# ARUDUINO128-3.net
KiCad netlist of a schematic drawn in EAGLE
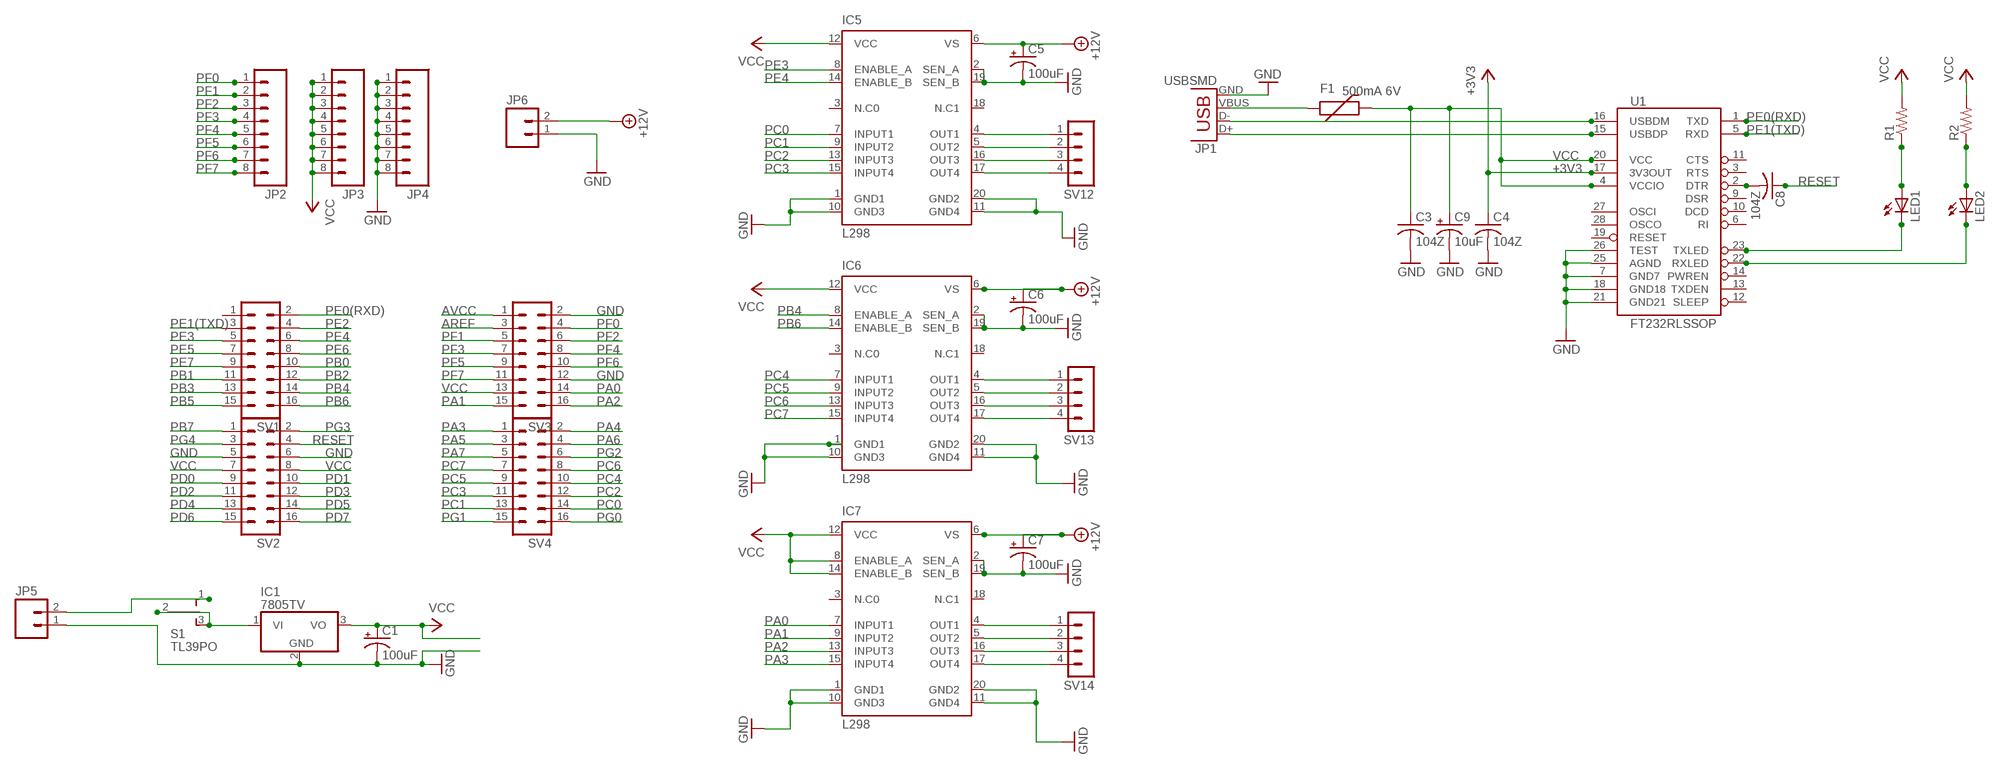
[diagram p0: schematic, sheet 1]

(export (version "E")
  (design (tool "Eeschema 10.0.6"))
  (components
    (comp (ref "C1")
      (value "100uF")
      (footprint "eagle-import:153CLV-0807")
      (libsource (lib "eagle-import") (part "CPOL-US153CLV-0807"))
    )
    (comp (ref "C3")
      (value "104Z")
      (footprint "eagle-import:C0603K")
      (libsource (lib "eagle-import") (part "C-USC0603K"))
    )
    (comp (ref "C4")
      (value "104Z")
      (footprint "eagle-import:C0603K")
      (libsource (lib "eagle-import") (part "C-USC0603K"))
    )
    (comp (ref "C5")
      (value "100uF")
      (footprint "eagle-import:153CLV-0807")
      (libsource (lib "eagle-import") (part "CPOL-US153CLV-0807"))
    )
    (comp (ref "C6")
      (value "100uF")
      (footprint "eagle-import:153CLV-0807")
      (libsource (lib "eagle-import") (part "CPOL-US153CLV-0807"))
    )
    (comp (ref "C7")
      (value "100uF")
      (footprint "eagle-import:153CLV-0807")
      (libsource (lib "eagle-import") (part "CPOL-US153CLV-0807"))
    )
    (comp (ref "C8")
      (value "104Z")
      (footprint "eagle-import:C0603K")
      (libsource (lib "eagle-import") (part "C-USC0603K"))
    )
    (comp (ref "C9")
      (value "10uF")
      (footprint "eagle-import:A_3216-18W")
      (libsource (lib "eagle-import") (part "CPOL-USA/3216-18W"))
    )
    (comp (ref "F1")
      (value "500mA 6V")
      (footprint "eagle-import:PTC-1206")
      (libsource (lib "eagle-import") (part "PTCSMD"))
    )
    (comp (ref "IC1")
      (value "7805TV")
      (footprint "eagle-import:TO220V")
      (libsource (lib "eagle-import") (part "78TV05"))
    )
    (comp (ref "IC5")
      (value "L298")
      (footprint "eagle-import:POWERSO-20")
      (libsource (lib "eagle-import") (part "L298"))
    )
    (comp (ref "IC6")
      (value "L298")
      (footprint "eagle-import:POWERSO-20")
      (libsource (lib "eagle-import") (part "L298"))
    )
    (comp (ref "IC7")
      (value "L298")
      (footprint "eagle-import:POWERSO-20")
      (libsource (lib "eagle-import") (part "L298"))
    )
    (comp (ref "JP1")
      (value "USBSMD")
      (footprint "eagle-import:USB-MINIB")
      (libsource (lib "eagle-import") (part "USBSMD"))
    )
    (comp (ref "JP2")
      (value "M08")
      (footprint "eagle-import:1X08_ROUND")
      (libsource (lib "eagle-import") (part "M08"))
    )
    (comp (ref "JP3")
      (value "M08")
      (footprint "eagle-import:1X08_ROUND")
      (libsource (lib "eagle-import") (part "M08"))
    )
    (comp (ref "JP4")
      (value "M08")
      (footprint "eagle-import:1X08_ROUND")
      (libsource (lib "eagle-import") (part "M08"))
    )
    (comp (ref "JP5")
      (value "M02PTH")
      (footprint "eagle-import:1X02")
      (libsource (lib "eagle-import") (part "M02PTH"))
    )
    (comp (ref "JP6")
      (value "M02PTH")
      (footprint "eagle-import:1X02")
      (libsource (lib "eagle-import") (part "M02PTH"))
    )
    (comp (ref "LED1")
      (value "LEDCHIPLED_0603")
      (footprint "eagle-import:CHIPLED_0603")
      (libsource (lib "eagle-import") (part "LEDCHIPLED_0603"))
    )
    (comp (ref "LED2")
      (value "LEDCHIPLED_0603")
      (footprint "eagle-import:CHIPLED_0603")
      (libsource (lib "eagle-import") (part "LEDCHIPLED_0603"))
    )
    (comp (ref "R1")
      (value "R-US_M0805")
      (footprint "eagle-import:M0805")
      (libsource (lib "eagle-import") (part "R-US_M0805"))
    )
    (comp (ref "R2")
      (value "R-US_M0805")
      (footprint "eagle-import:M0805")
      (libsource (lib "eagle-import") (part "R-US_M0805"))
    )
    (comp (ref "S1")
      (value "TL39PO")
      (footprint "eagle-import:TL3XPO")
      (libsource (lib "eagle-import") (part "TL39PO"))
    )
    (comp (ref "SV1")
      (value "MA08-2")
      (footprint "eagle-import:MA08-2")
      (libsource (lib "eagle-import") (part "MA08-2"))
    )
    (comp (ref "SV2")
      (value "MA08-2")
      (footprint "eagle-import:MA08-2")
      (libsource (lib "eagle-import") (part "MA08-2"))
    )
    (comp (ref "SV3")
      (value "MA08-2")
      (footprint "eagle-import:MA08-2")
      (libsource (lib "eagle-import") (part "MA08-2"))
    )
    (comp (ref "SV4")
      (value "MA08-2")
      (footprint "eagle-import:MA08-2")
      (libsource (lib "eagle-import") (part "MA08-2"))
    )
    (comp (ref "SV12")
      (value "MA04-1")
      (footprint "eagle-import:MA04-1")
      (libsource (lib "eagle-import") (part "MA04-1"))
    )
    (comp (ref "SV13")
      (value "MA04-1")
      (footprint "eagle-import:MA04-1")
      (libsource (lib "eagle-import") (part "MA04-1"))
    )
    (comp (ref "SV14")
      (value "MA04-1")
      (footprint "eagle-import:MA04-1")
      (libsource (lib "eagle-import") (part "MA04-1"))
    )
    (comp (ref "U1")
      (value "FT232RLSSOP")
      (footprint "eagle-import:SSOP28DB")
      (libsource (lib "eagle-import") (part "FT232RLSSOP"))
    )
  )
  (nets
    (net (code "1") (name "+3V3") (class "Default")
      (node (ref "C4") (pin "1") (pinfunction "1_1") (pintype "passive"))
      (node (ref "U1") (pin "17") (pinfunction "3V3OUT_17") (pintype "output"))
    )
    (net (code "2") (name "+12V") (class "Default")
      (node (ref "C5") (pin "+") (pinfunction "+_+") (pintype "passive"))
      (node (ref "C6") (pin "+") (pinfunction "+_+") (pintype "passive"))
      (node (ref "C7") (pin "+") (pinfunction "+_+") (pintype "passive"))
      (node (ref "IC5") (pin "6") (pinfunction "VS_6") (pintype "power_in"))
      (node (ref "IC6") (pin "6") (pinfunction "VS_6") (pintype "power_in"))
      (node (ref "IC7") (pin "6") (pinfunction "VS_6") (pintype "power_in"))
      (node (ref "JP6") (pin "2") (pinfunction "2_2") (pintype "passive"))
    )
    (net (code "3") (name "/AREF") (class "Default")
      (node (ref "SV3") (pin "3") (pinfunction "3_3") (pintype "passive"))
    )
    (net (code "4") (name "/AVCC") (class "Default")
      (node (ref "SV3") (pin "1") (pinfunction "1_1") (pintype "passive"))
    )
    (net (code "5") (name "/PA0") (class "Default")
      (node (ref "IC7") (pin "7") (pinfunction "INPUT1_7") (pintype "input"))
      (node (ref "SV3") (pin "14") (pinfunction "14_14") (pintype "passive"))
    )
    (net (code "6") (name "/PA1") (class "Default")
      (node (ref "IC7") (pin "9") (pinfunction "INPUT2_9") (pintype "input"))
      (node (ref "SV3") (pin "15") (pinfunction "15_15") (pintype "passive"))
    )
    (net (code "7") (name "/PA2") (class "Default")
      (node (ref "IC7") (pin "13") (pinfunction "INPUT3_13") (pintype "input"))
      (node (ref "SV3") (pin "16") (pinfunction "16_16") (pintype "passive"))
    )
    (net (code "8") (name "/PA3") (class "Default")
      (node (ref "IC7") (pin "15") (pinfunction "INPUT4_15") (pintype "input"))
      (node (ref "SV4") (pin "1") (pinfunction "1_1") (pintype "passive"))
    )
    (net (code "9") (name "/PA4") (class "Default")
      (node (ref "SV4") (pin "2") (pinfunction "2_2") (pintype "passive"))
    )
    (net (code "10") (name "/PA5") (class "Default")
      (node (ref "SV4") (pin "3") (pinfunction "3_3") (pintype "passive"))
    )
    (net (code "11") (name "/PA6") (class "Default")
      (node (ref "SV4") (pin "4") (pinfunction "4_4") (pintype "passive"))
    )
    (net (code "12") (name "/PA7") (class "Default")
      (node (ref "SV4") (pin "5") (pinfunction "5_5") (pintype "passive"))
    )
    (net (code "13") (name "/PB0") (class "Default")
      (node (ref "SV1") (pin "10") (pinfunction "10_10") (pintype "passive"))
    )
    (net (code "14") (name "/PB1") (class "Default")
      (node (ref "SV1") (pin "11") (pinfunction "11_11") (pintype "passive"))
    )
    (net (code "15") (name "/PB2") (class "Default")
      (node (ref "SV1") (pin "12") (pinfunction "12_12") (pintype "passive"))
    )
    (net (code "16") (name "/PB3") (class "Default")
      (node (ref "SV1") (pin "13") (pinfunction "13_13") (pintype "passive"))
    )
    (net (code "17") (name "/PB4") (class "Default")
      (node (ref "IC6") (pin "8") (pinfunction "ENABLE_A_8") (pintype "input"))
      (node (ref "SV1") (pin "14") (pinfunction "14_14") (pintype "passive"))
    )
    (net (code "18") (name "/PB5") (class "Default")
      (node (ref "SV1") (pin "15") (pinfunction "15_15") (pintype "passive"))
    )
    (net (code "19") (name "/PB6") (class "Default")
      (node (ref "IC6") (pin "14") (pinfunction "ENABLE_B_14") (pintype "input"))
      (node (ref "SV1") (pin "16") (pinfunction "16_16") (pintype "passive"))
    )
    (net (code "20") (name "/PB7") (class "Default")
      (node (ref "SV2") (pin "1") (pinfunction "1_1") (pintype "passive"))
    )
    (net (code "21") (name "/PC0") (class "Default")
      (node (ref "IC5") (pin "7") (pinfunction "INPUT1_7") (pintype "input"))
      (node (ref "SV4") (pin "14") (pinfunction "14_14") (pintype "passive"))
    )
    (net (code "22") (name "/PC1") (class "Default")
      (node (ref "IC5") (pin "9") (pinfunction "INPUT2_9") (pintype "input"))
      (node (ref "SV4") (pin "13") (pinfunction "13_13") (pintype "passive"))
    )
    (net (code "23") (name "/PC2") (class "Default")
      (node (ref "IC5") (pin "13") (pinfunction "INPUT3_13") (pintype "input"))
      (node (ref "SV4") (pin "12") (pinfunction "12_12") (pintype "passive"))
    )
    (net (code "24") (name "/PC3") (class "Default")
      (node (ref "IC5") (pin "15") (pinfunction "INPUT4_15") (pintype "input"))
      (node (ref "SV4") (pin "11") (pinfunction "11_11") (pintype "passive"))
    )
    (net (code "25") (name "/PC4") (class "Default")
      (node (ref "IC6") (pin "7") (pinfunction "INPUT1_7") (pintype "input"))
      (node (ref "SV4") (pin "10") (pinfunction "10_10") (pintype "passive"))
    )
    (net (code "26") (name "/PC5") (class "Default")
      (node (ref "IC6") (pin "9") (pinfunction "INPUT2_9") (pintype "input"))
      (node (ref "SV4") (pin "9") (pinfunction "9_9") (pintype "passive"))
    )
    (net (code "27") (name "/PC6") (class "Default")
      (node (ref "IC6") (pin "13") (pinfunction "INPUT3_13") (pintype "input"))
      (node (ref "SV4") (pin "8") (pinfunction "8_8") (pintype "passive"))
    )
    (net (code "28") (name "/PC7") (class "Default")
      (node (ref "IC6") (pin "15") (pinfunction "INPUT4_15") (pintype "input"))
      (node (ref "SV4") (pin "7") (pinfunction "7_7") (pintype "passive"))
    )
    (net (code "29") (name "/PD0") (class "Default")
      (node (ref "SV2") (pin "9") (pinfunction "9_9") (pintype "passive"))
    )
    (net (code "30") (name "/PD1") (class "Default")
      (node (ref "SV2") (pin "10") (pinfunction "10_10") (pintype "passive"))
    )
    (net (code "31") (name "/PD2") (class "Default")
      (node (ref "SV2") (pin "11") (pinfunction "11_11") (pintype "passive"))
    )
    (net (code "32") (name "/PD3") (class "Default")
      (node (ref "SV2") (pin "12") (pinfunction "12_12") (pintype "passive"))
    )
    (net (code "33") (name "/PD4") (class "Default")
      (node (ref "SV2") (pin "13") (pinfunction "13_13") (pintype "passive"))
    )
    (net (code "34") (name "/PD5") (class "Default")
      (node (ref "SV2") (pin "14") (pinfunction "14_14") (pintype "passive"))
    )
    (net (code "35") (name "/PD6") (class "Default")
      (node (ref "SV2") (pin "15") (pinfunction "15_15") (pintype "passive"))
    )
    (net (code "36") (name "/PD7") (class "Default")
      (node (ref "SV2") (pin "16") (pinfunction "16_16") (pintype "passive"))
    )
    (net (code "37") (name "/PE0(RXD)") (class "Default")
      (node (ref "SV1") (pin "2") (pinfunction "2_2") (pintype "passive"))
      (node (ref "U1") (pin "1") (pinfunction "TXD_1") (pintype "output"))
    )
    (net (code "38") (name "/PE1(TXD)") (class "Default")
      (node (ref "SV1") (pin "3") (pinfunction "3_3") (pintype "passive"))
      (node (ref "U1") (pin "5") (pinfunction "RXD_5") (pintype "input"))
    )
    (net (code "39") (name "/PE2") (class "Default")
      (node (ref "SV1") (pin "4") (pinfunction "4_4") (pintype "passive"))
    )
    (net (code "40") (name "/PE3") (class "Default")
      (node (ref "IC5") (pin "8") (pinfunction "ENABLE_A_8") (pintype "input"))
      (node (ref "SV1") (pin "5") (pinfunction "5_5") (pintype "passive"))
    )
    (net (code "41") (name "/PE4") (class "Default")
      (node (ref "IC5") (pin "14") (pinfunction "ENABLE_B_14") (pintype "input"))
      (node (ref "SV1") (pin "6") (pinfunction "6_6") (pintype "passive"))
    )
    (net (code "42") (name "/PE5") (class "Default")
      (node (ref "SV1") (pin "7") (pinfunction "7_7") (pintype "passive"))
    )
    (net (code "43") (name "/PE6") (class "Default")
      (node (ref "SV1") (pin "8") (pinfunction "8_8") (pintype "passive"))
    )
    (net (code "44") (name "/PE7") (class "Default")
      (node (ref "SV1") (pin "9") (pinfunction "9_9") (pintype "passive"))
    )
    (net (code "45") (name "/PF0") (class "Default")
      (node (ref "JP2") (pin "1") (pinfunction "1_1") (pintype "passive"))
      (node (ref "SV3") (pin "4") (pinfunction "4_4") (pintype "passive"))
    )
    (net (code "46") (name "/PF1") (class "Default")
      (node (ref "JP2") (pin "2") (pinfunction "2_2") (pintype "passive"))
      (node (ref "SV3") (pin "5") (pinfunction "5_5") (pintype "passive"))
    )
    (net (code "47") (name "/PF2") (class "Default")
      (node (ref "JP2") (pin "3") (pinfunction "3_3") (pintype "passive"))
      (node (ref "SV3") (pin "6") (pinfunction "6_6") (pintype "passive"))
    )
    (net (code "48") (name "/PF3") (class "Default")
      (node (ref "JP2") (pin "4") (pinfunction "4_4") (pintype "passive"))
      (node (ref "SV3") (pin "7") (pinfunction "7_7") (pintype "passive"))
    )
    (net (code "49") (name "/PF4") (class "Default")
      (node (ref "JP2") (pin "5") (pinfunction "5_5") (pintype "passive"))
      (node (ref "SV3") (pin "8") (pinfunction "8_8") (pintype "passive"))
    )
    (net (code "50") (name "/PF5") (class "Default")
      (node (ref "JP2") (pin "6") (pinfunction "6_6") (pintype "passive"))
      (node (ref "SV3") (pin "9") (pinfunction "9_9") (pintype "passive"))
    )
    (net (code "51") (name "/PF6") (class "Default")
      (node (ref "JP2") (pin "7") (pinfunction "7_7") (pintype "passive"))
      (node (ref "SV3") (pin "10") (pinfunction "10_10") (pintype "passive"))
    )
    (net (code "52") (name "/PF7") (class "Default")
      (node (ref "JP2") (pin "8") (pinfunction "8_8") (pintype "passive"))
      (node (ref "SV3") (pin "11") (pinfunction "11_11") (pintype "passive"))
    )
    (net (code "53") (name "/PG0") (class "Default")
      (node (ref "SV4") (pin "16") (pinfunction "16_16") (pintype "passive"))
    )
    (net (code "54") (name "/PG1") (class "Default")
      (node (ref "SV4") (pin "15") (pinfunction "15_15") (pintype "passive"))
    )
    (net (code "55") (name "/PG2") (class "Default")
      (node (ref "SV4") (pin "6") (pinfunction "6_6") (pintype "passive"))
    )
    (net (code "56") (name "/PG3") (class "Default")
      (node (ref "SV2") (pin "2") (pinfunction "2_2") (pintype "passive"))
    )
    (net (code "57") (name "/PG4") (class "Default")
      (node (ref "SV2") (pin "3") (pinfunction "3_3") (pintype "passive"))
    )
    (net (code "58") (name "/RESET") (class "Default")
      (node (ref "C8") (pin "1") (pinfunction "1_1") (pintype "passive"))
      (node (ref "SV2") (pin "4") (pinfunction "4_4") (pintype "passive"))
    )
    (net (code "59") (name "GND") (class "Default")
      (node (ref "C1") (pin "-") (pinfunction "-_-") (pintype "passive"))
      (node (ref "C3") (pin "2") (pinfunction "2_2") (pintype "passive"))
      (node (ref "C4") (pin "2") (pinfunction "2_2") (pintype "passive"))
      (node (ref "C5") (pin "-") (pinfunction "-_-") (pintype "passive"))
      (node (ref "C6") (pin "-") (pinfunction "-_-") (pintype "passive"))
      (node (ref "C7") (pin "-") (pinfunction "-_-") (pintype "passive"))
      (node (ref "C9") (pin "-") (pinfunction "-_-") (pintype "passive"))
      (node (ref "IC1") (pin "2") (pinfunction "GND_2") (pintype "passive"))
      (node (ref "IC5") (pin "1") (pinfunction "GND1_1") (pintype "power_in"))
      (node (ref "IC5") (pin "10") (pinfunction "GND3_10") (pintype "power_in"))
      (node (ref "IC5") (pin "11") (pinfunction "GND4_11") (pintype "power_in"))
      (node (ref "IC5") (pin "19") (pinfunction "SEN_B_19") (pintype "input"))
      (node (ref "IC5") (pin "2") (pinfunction "SEN_A_2") (pintype "input"))
      (node (ref "IC5") (pin "20") (pinfunction "GND2_20") (pintype "power_in"))
      (node (ref "IC6") (pin "1") (pinfunction "GND1_1") (pintype "power_in"))
      (node (ref "IC6") (pin "10") (pinfunction "GND3_10") (pintype "power_in"))
      (node (ref "IC6") (pin "11") (pinfunction "GND4_11") (pintype "power_in"))
      (node (ref "IC6") (pin "19") (pinfunction "SEN_B_19") (pintype "input"))
      (node (ref "IC6") (pin "2") (pinfunction "SEN_A_2") (pintype "input"))
      (node (ref "IC6") (pin "20") (pinfunction "GND2_20") (pintype "power_in"))
      (node (ref "IC7") (pin "1") (pinfunction "GND1_1") (pintype "power_in"))
      (node (ref "IC7") (pin "10") (pinfunction "GND3_10") (pintype "power_in"))
      (node (ref "IC7") (pin "11") (pinfunction "GND4_11") (pintype "power_in"))
      (node (ref "IC7") (pin "19") (pinfunction "SEN_B_19") (pintype "input"))
      (node (ref "IC7") (pin "2") (pinfunction "SEN_A_2") (pintype "input"))
      (node (ref "IC7") (pin "20") (pinfunction "GND2_20") (pintype "power_in"))
      (node (ref "JP1") (pin "GND") (pinfunction "GND_GND") (pintype "bidirectional"))
      (node (ref "JP4") (pin "1") (pinfunction "1_1") (pintype "passive"))
      (node (ref "JP4") (pin "2") (pinfunction "2_2") (pintype "passive"))
      (node (ref "JP4") (pin "3") (pinfunction "3_3") (pintype "passive"))
      (node (ref "JP4") (pin "4") (pinfunction "4_4") (pintype "passive"))
      (node (ref "JP4") (pin "5") (pinfunction "5_5") (pintype "passive"))
      (node (ref "JP4") (pin "6") (pinfunction "6_6") (pintype "passive"))
      (node (ref "JP4") (pin "7") (pinfunction "7_7") (pintype "passive"))
      (node (ref "JP4") (pin "8") (pinfunction "8_8") (pintype "passive"))
      (node (ref "JP5") (pin "1") (pinfunction "1_1") (pintype "passive"))
      (node (ref "JP6") (pin "1") (pinfunction "1_1") (pintype "passive"))
      (node (ref "SV2") (pin "5") (pinfunction "5_5") (pintype "passive"))
      (node (ref "SV2") (pin "6") (pinfunction "6_6") (pintype "passive"))
      (node (ref "SV3") (pin "12") (pinfunction "12_12") (pintype "passive"))
      (node (ref "SV3") (pin "2") (pinfunction "2_2") (pintype "passive"))
      (node (ref "U1") (pin "18") (pinfunction "GND18_18") (pintype "power_in"))
      (node (ref "U1") (pin "21") (pinfunction "GND21_21") (pintype "power_in"))
      (node (ref "U1") (pin "25") (pinfunction "AGND_25") (pintype "power_in"))
      (node (ref "U1") (pin "26") (pinfunction "TEST_26") (pintype "input"))
      (node (ref "U1") (pin "7") (pinfunction "GND7_7") (pintype "power_in"))
    )
    (net (code "60") (name "Net-(F1-Pad1)") (class "Default")
      (node (ref "F1") (pin "1") (pinfunction "1_1") (pintype "bidirectional"))
      (node (ref "JP1") (pin "VBUS") (pinfunction "VBUS_VBUS") (pintype "bidirectional"))
    )
    (net (code "61") (name "Net-(IC1-VI)") (class "Default")
      (node (ref "IC1") (pin "1") (pinfunction "VI_1") (pintype "input"))
      (node (ref "S1") (pin "2") (pinfunction "P_2") (pintype "passive"))
      (node (ref "S1") (pin "3") (pinfunction "S_3") (pintype "passive"))
    )
    (net (code "62") (name "Net-(IC5-OUT1)") (class "Default")
      (node (ref "IC5") (pin "4") (pinfunction "OUT1_4") (pintype "output"))
      (node (ref "SV12") (pin "1") (pinfunction "1_1") (pintype "passive"))
    )
    (net (code "63") (name "Net-(IC5-OUT2)") (class "Default")
      (node (ref "IC5") (pin "5") (pinfunction "OUT2_5") (pintype "output"))
      (node (ref "SV12") (pin "2") (pinfunction "2_2") (pintype "passive"))
    )
    (net (code "64") (name "Net-(IC5-OUT3)") (class "Default")
      (node (ref "IC5") (pin "16") (pinfunction "OUT3_16") (pintype "output"))
      (node (ref "SV12") (pin "3") (pinfunction "3_3") (pintype "passive"))
    )
    (net (code "65") (name "Net-(IC5-OUT4)") (class "Default")
      (node (ref "IC5") (pin "17") (pinfunction "OUT4_17") (pintype "output"))
      (node (ref "SV12") (pin "4") (pinfunction "4_4") (pintype "passive"))
    )
    (net (code "66") (name "Net-(IC6-OUT1)") (class "Default")
      (node (ref "IC6") (pin "4") (pinfunction "OUT1_4") (pintype "output"))
      (node (ref "SV13") (pin "1") (pinfunction "1_1") (pintype "passive"))
    )
    (net (code "67") (name "Net-(IC6-OUT2)") (class "Default")
      (node (ref "IC6") (pin "5") (pinfunction "OUT2_5") (pintype "output"))
      (node (ref "SV13") (pin "2") (pinfunction "2_2") (pintype "passive"))
    )
    (net (code "68") (name "Net-(IC6-OUT3)") (class "Default")
      (node (ref "IC6") (pin "16") (pinfunction "OUT3_16") (pintype "output"))
      (node (ref "SV13") (pin "3") (pinfunction "3_3") (pintype "passive"))
    )
    (net (code "69") (name "Net-(IC6-OUT4)") (class "Default")
      (node (ref "IC6") (pin "17") (pinfunction "OUT4_17") (pintype "output"))
      (node (ref "SV13") (pin "4") (pinfunction "4_4") (pintype "passive"))
    )
    (net (code "70") (name "Net-(IC7-OUT1)") (class "Default")
      (node (ref "IC7") (pin "4") (pinfunction "OUT1_4") (pintype "output"))
      (node (ref "SV14") (pin "1") (pinfunction "1_1") (pintype "passive"))
    )
    (net (code "71") (name "Net-(IC7-OUT2)") (class "Default")
      (node (ref "IC7") (pin "5") (pinfunction "OUT2_5") (pintype "output"))
      (node (ref "SV14") (pin "2") (pinfunction "2_2") (pintype "passive"))
    )
    (net (code "72") (name "Net-(IC7-OUT3)") (class "Default")
      (node (ref "IC7") (pin "16") (pinfunction "OUT3_16") (pintype "output"))
      (node (ref "SV14") (pin "3") (pinfunction "3_3") (pintype "passive"))
    )
    (net (code "73") (name "Net-(IC7-OUT4)") (class "Default")
      (node (ref "IC7") (pin "17") (pinfunction "OUT4_17") (pintype "output"))
      (node (ref "SV14") (pin "4") (pinfunction "4_4") (pintype "passive"))
    )
    (net (code "74") (name "Net-(LED1-PadA)") (class "Default")
      (node (ref "LED1") (pin "A") (pinfunction "A_A") (pintype "passive"))
      (node (ref "R1") (pin "1") (pinfunction "1_1") (pintype "passive"))
    )
    (net (code "75") (name "Net-(LED2-PadA)") (class "Default")
      (node (ref "LED2") (pin "A") (pinfunction "A_A") (pintype "passive"))
      (node (ref "R2") (pin "1") (pinfunction "1_1") (pintype "passive"))
    )
    (net (code "76") (name "Net-(S1-O)") (class "Default")
      (node (ref "JP5") (pin "2") (pinfunction "2_2") (pintype "passive"))
      (node (ref "S1") (pin "1") (pinfunction "O_1") (pintype "passive"))
    )
    (net (code "77") (name "Net-(U1-DTR)") (class "Default")
      (node (ref "C8") (pin "2") (pinfunction "2_2") (pintype "passive"))
      (node (ref "U1") (pin "2") (pinfunction "DTR_2") (pintype "output"))
    )
    (net (code "78") (name "Net-(U1-RXLED)") (class "Default")
      (node (ref "LED2") (pin "C") (pinfunction "C_C") (pintype "passive"))
      (node (ref "U1") (pin "22") (pinfunction "RXLED_22") (pintype "input"))
    )
    (net (code "79") (name "Net-(U1-TXLED)") (class "Default")
      (node (ref "LED1") (pin "C") (pinfunction "C_C") (pintype "passive"))
      (node (ref "U1") (pin "23") (pinfunction "TXLED_23") (pintype "input"))
    )
    (net (code "80") (name "Net-(U1-USBDM)") (class "Default")
      (node (ref "JP1") (pin "D-") (pinfunction "D-_D-") (pintype "bidirectional"))
      (node (ref "U1") (pin "16") (pinfunction "USBDM_16") (pintype "bidirectional"))
    )
    (net (code "81") (name "Net-(U1-USBDP)") (class "Default")
      (node (ref "JP1") (pin "D+") (pinfunction "D+_D+") (pintype "bidirectional"))
      (node (ref "U1") (pin "15") (pinfunction "USBDP_15") (pintype "bidirectional"))
    )
    (net (code "82") (name "VCC") (class "Default")
      (node (ref "C1") (pin "+") (pinfunction "+_+") (pintype "passive"))
      (node (ref "C3") (pin "1") (pinfunction "1_1") (pintype "passive"))
      (node (ref "C9") (pin "+") (pinfunction "+_+") (pintype "passive"))
      (node (ref "F1") (pin "2") (pinfunction "2_2") (pintype "bidirectional"))
      (node (ref "IC1") (pin "3") (pinfunction "VO_3") (pintype "passive"))
      (node (ref "IC5") (pin "12") (pinfunction "VCC_12") (pintype "power_in"))
      (node (ref "IC6") (pin "12") (pinfunction "VCC_12") (pintype "power_in"))
      (node (ref "IC7") (pin "12") (pinfunction "VCC_12") (pintype "power_in"))
      (node (ref "IC7") (pin "14") (pinfunction "ENABLE_B_14") (pintype "input"))
      (node (ref "IC7") (pin "8") (pinfunction "ENABLE_A_8") (pintype "input"))
      (node (ref "JP3") (pin "1") (pinfunction "1_1") (pintype "passive"))
      (node (ref "JP3") (pin "2") (pinfunction "2_2") (pintype "passive"))
      (node (ref "JP3") (pin "3") (pinfunction "3_3") (pintype "passive"))
      (node (ref "JP3") (pin "4") (pinfunction "4_4") (pintype "passive"))
      (node (ref "JP3") (pin "5") (pinfunction "5_5") (pintype "passive"))
      (node (ref "JP3") (pin "6") (pinfunction "6_6") (pintype "passive"))
      (node (ref "JP3") (pin "7") (pinfunction "7_7") (pintype "passive"))
      (node (ref "JP3") (pin "8") (pinfunction "8_8") (pintype "passive"))
      (node (ref "R1") (pin "2") (pinfunction "2_2") (pintype "passive"))
      (node (ref "R2") (pin "2") (pinfunction "2_2") (pintype "passive"))
      (node (ref "SV2") (pin "7") (pinfunction "7_7") (pintype "passive"))
      (node (ref "SV2") (pin "8") (pinfunction "8_8") (pintype "passive"))
      (node (ref "SV3") (pin "13") (pinfunction "13_13") (pintype "passive"))
      (node (ref "U1") (pin "20") (pinfunction "VCC_20") (pintype "power_in"))
      (node (ref "U1") (pin "4") (pinfunction "VCCIO_4") (pintype "power_in"))
    )
    (net (code "83") (name "unconnected-(IC5-N.C0-Pad3)") (class "Default")
      (node (ref "IC5") (pin "3") (pinfunction "N.C0_3") (pintype "no_connect"))
    )
    (net (code "84") (name "unconnected-(IC5-N.C1-Pad18)") (class "Default")
      (node (ref "IC5") (pin "18") (pinfunction "N.C1_18") (pintype "no_connect"))
    )
    (net (code "85") (name "unconnected-(IC6-N.C0-Pad3)") (class "Default")
      (node (ref "IC6") (pin "3") (pinfunction "N.C0_3") (pintype "no_connect"))
    )
    (net (code "86") (name "unconnected-(IC6-N.C1-Pad18)") (class "Default")
      (node (ref "IC6") (pin "18") (pinfunction "N.C1_18") (pintype "no_connect"))
    )
    (net (code "87") (name "unconnected-(IC7-N.C0-Pad3)") (class "Default")
      (node (ref "IC7") (pin "3") (pinfunction "N.C0_3") (pintype "no_connect"))
    )
    (net (code "88") (name "unconnected-(IC7-N.C1-Pad18)") (class "Default")
      (node (ref "IC7") (pin "18") (pinfunction "N.C1_18") (pintype "no_connect"))
    )
    (net (code "89") (name "unconnected-(SV1-Pad1)") (class "Default")
      (node (ref "SV1") (pin "1") (pinfunction "1_1") (pintype "passive"))
    )
    (net (code "90") (name "unconnected-(U1-CTS-Pad11)") (class "Default")
      (node (ref "U1") (pin "11") (pinfunction "CTS_11") (pintype "input"))
    )
    (net (code "91") (name "unconnected-(U1-DCD-Pad10)") (class "Default")
      (node (ref "U1") (pin "10") (pinfunction "DCD_10") (pintype "input"))
    )
    (net (code "92") (name "unconnected-(U1-DSR-Pad9)") (class "Default")
      (node (ref "U1") (pin "9") (pinfunction "DSR_9") (pintype "input"))
    )
    (net (code "93") (name "unconnected-(U1-OSCI-Pad27)") (class "Default")
      (node (ref "U1") (pin "27") (pinfunction "OSCI_27") (pintype "input"))
    )
    (net (code "94") (name "unconnected-(U1-OSCO-Pad28)") (class "Default")
      (node (ref "U1") (pin "28") (pinfunction "OSCO_28") (pintype "output"))
    )
    (net (code "95") (name "unconnected-(U1-PWREN-Pad14)") (class "Default")
      (node (ref "U1") (pin "14") (pinfunction "PWREN_14") (pintype "input"))
    )
    (net (code "96") (name "unconnected-(U1-RESET-Pad19)") (class "Default")
      (node (ref "U1") (pin "19") (pinfunction "RESET_19") (pintype "input"))
    )
    (net (code "97") (name "unconnected-(U1-RI-Pad6)") (class "Default")
      (node (ref "U1") (pin "6") (pinfunction "RI_6") (pintype "input"))
    )
    (net (code "98") (name "unconnected-(U1-RTS-Pad3)") (class "Default")
      (node (ref "U1") (pin "3") (pinfunction "RTS_3") (pintype "output"))
    )
    (net (code "99") (name "unconnected-(U1-SLEEP-Pad12)") (class "Default")
      (node (ref "U1") (pin "12") (pinfunction "SLEEP_12") (pintype "input"))
    )
    (net (code "100") (name "unconnected-(U1-TXDEN-Pad13)") (class "Default")
      (node (ref "U1") (pin "13") (pinfunction "TXDEN_13") (pintype "input"))
    )
  )
)
